# ESP32.net
KiCad netlist of a schematic drawn in EAGLE
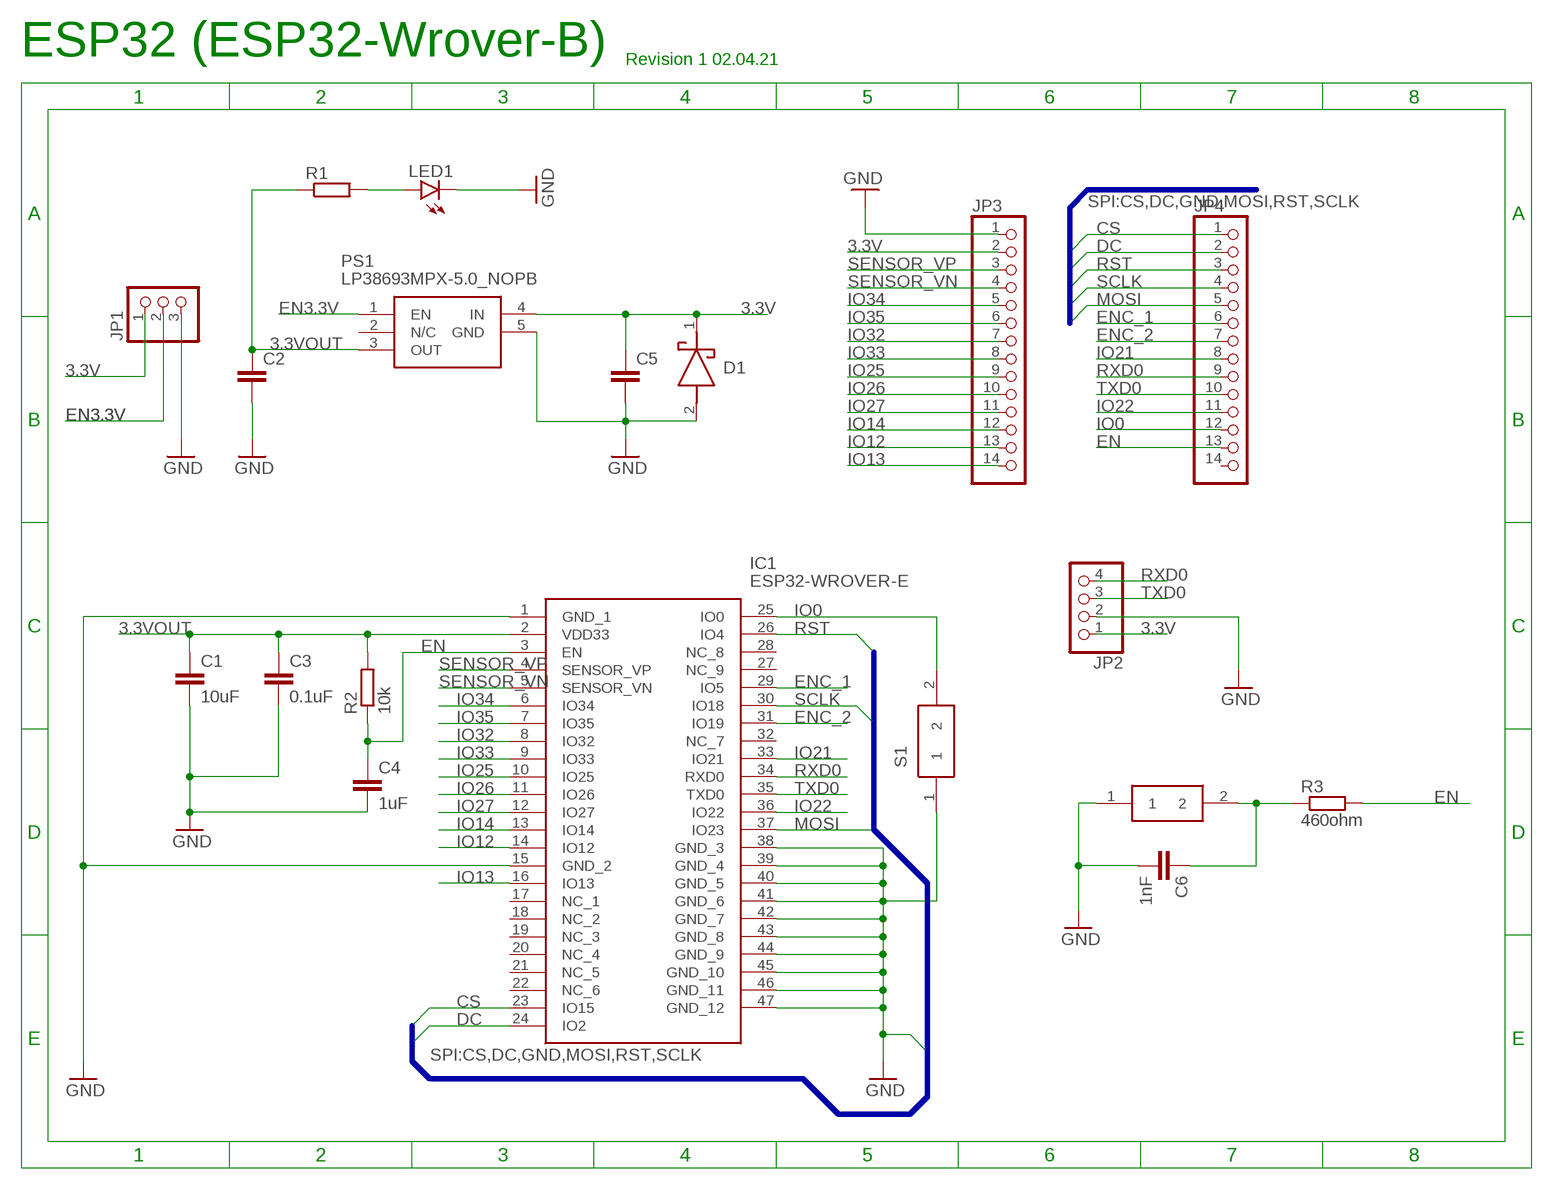
[diagram p0: schematic, sheet 1]

(export (version "E")
  (design (tool "Eeschema 10.0.6"))
  (components
    (comp (ref "C1")
      (value "10uF")
      (footprint "eagle-import:C1206")
      (libsource (lib "eagle-import") (part "C-EU_1206C1206"))
    )
    (comp (ref "C2")
      (value "C-EUC0805")
      (footprint "eagle-import:C0805")
      (libsource (lib "eagle-import") (part "C-EUC0805"))
    )
    (comp (ref "C3")
      (value "0.1uF")
      (footprint "eagle-import:C0805")
      (libsource (lib "eagle-import") (part "C-EU_805C0805"))
    )
    (comp (ref "C4")
      (value "1uF")
      (footprint "eagle-import:C0805")
      (libsource (lib "eagle-import") (part "C-EU_805C0805"))
    )
    (comp (ref "C5")
      (value "C-EUC0805")
      (footprint "eagle-import:C0805")
      (libsource (lib "eagle-import") (part "C-EUC0805"))
    )
    (comp (ref "C6")
      (value "1nF")
      (footprint "eagle-import:C0805")
      (libsource (lib "eagle-import") (part "C-EU_805C0805"))
    )
    (comp (ref "D1")
      (value "LSM115JE3_TR13")
      (footprint "eagle-import:DIOM5436X330N")
      (fields
        (field (name "MANUFACTURER_PART_NUMBER") "LSM115JE3/TR13")
        (field (name "MOUSER_PART_NUMBER") "494-LSM115JE3/TR13")
      )
      (libsource (lib "eagle-import") (part "LSM115JE3_TR13"))
    )
    (comp (ref "IC1")
      (value "ESP32-WROVER-E")
      (footprint "eagle-import:ESP32WROVERBM213DH6464PC3Q0")
      (fields (field (name "MANUFACTURER_PART_NUMBER") "ESP32-WROVER-E(M213EH3264PH3Q0) "))
      (libsource (lib "eagle-import") (part "ESP32-WROVER-E"))
    )
    (comp (ref "JP1")
      (value "PINHD-1X3")
      (footprint "eagle-import:1X03")
      (libsource (lib "eagle-import") (part "PINHD-1X3"))
    )
    (comp (ref "JP2")
      (value "PINHD-1X4")
      (footprint "eagle-import:1X04")
      (libsource (lib "eagle-import") (part "PINHD-1X4"))
    )
    (comp (ref "JP3")
      (value "PINHD-1X14")
      (footprint "eagle-import:1X14")
      (libsource (lib "eagle-import") (part "PINHD-1X14"))
    )
    (comp (ref "JP4")
      (value "PINHD-1X14")
      (footprint "eagle-import:1X14")
      (libsource (lib "eagle-import") (part "PINHD-1X14"))
    )
    (comp (ref "LED1")
      (value "LED_1206SMT1206")
      (footprint "eagle-import:1206")
      (libsource (lib "eagle-import") (part "LED_1206SMT1206"))
    )
    (comp (ref "PS1")
      (value "LP38693MPX-5.0_NOPB")
      (footprint "eagle-import:SOT150P700X160-5N")
      (libsource (lib "eagle-import") (part "LP38693MPX-5.0_NOPB"))
    )
    (comp (ref "R1")
      (value "R-EU_R0805")
      (footprint "eagle-import:R0805")
      (libsource (lib "eagle-import") (part "R-EU_R0805"))
    )
    (comp (ref "R2")
      (value "10k")
      (footprint "eagle-import:R0805")
      (libsource (lib "eagle-import") (part "R-EU_805R0805"))
    )
    (comp (ref "R3")
      (value "460ohm")
      (footprint "eagle-import:R0805")
      (libsource (lib "eagle-import") (part "R-EU_805R0805"))
    )
    (comp (ref "S1")
      (value "FSMSMTR")
      (footprint "eagle-import:FSMSM")
      (fields (field (name "MOUSER_PART_NUMBER") "506-FSMSMTR") (field (name "RS_PART_NUMBER") "1680547"))
      (libsource (lib "eagle-import") (part "FSMSMTR"))
    )
    (comp (ref "S2")
      (value "FSMSMTR")
      (footprint "eagle-import:FSMSM")
      (fields (field (name "MOUSER_PART_NUMBER") "506-FSMSMTR") (field (name "RS_PART_NUMBER") "1680547"))
      (libsource (lib "eagle-import") (part "FSMSMTR"))
    )
  )
  (nets
    (net (code "2") (name "/3.3V") (class "Default")
      (node (ref "C5") (pin "1") (pinfunction "1_1") (pintype "passive"))
      (node (ref "D1") (pin "1") (pinfunction "K_1") (pintype "bidirectional"))
      (node (ref "JP1") (pin "1") (pinfunction "1_1") (pintype "passive"))
      (node (ref "JP2") (pin "1") (pinfunction "1_1") (pintype "passive"))
      (node (ref "JP3") (pin "2") (pinfunction "2_2") (pintype "passive"))
      (node (ref "PS1") (pin "4") (pinfunction "IN_4") (pintype "bidirectional"))
    )
    (net (code "3") (name "/3.3VOUT") (class "Default")
      (node (ref "C1") (pin "1") (pinfunction "1_1") (pintype "passive"))
      (node (ref "C2") (pin "1") (pinfunction "1_1") (pintype "passive"))
      (node (ref "C3") (pin "1") (pinfunction "1_1") (pintype "passive"))
      (node (ref "IC1") (pin "2") (pinfunction "VDD33_2") (pintype "bidirectional"))
      (node (ref "PS1") (pin "3") (pinfunction "OUT_3") (pintype "bidirectional"))
      (node (ref "R1") (pin "1") (pinfunction "1_1") (pintype "passive"))
      (node (ref "R2") (pin "2") (pinfunction "2_2") (pintype "passive"))
    )
    (net (code "4") (name "/CS") (class "Default")
      (node (ref "IC1") (pin "23") (pinfunction "IO15_23") (pintype "bidirectional"))
      (node (ref "JP4") (pin "1") (pinfunction "1_1") (pintype "passive"))
    )
    (net (code "5") (name "/DC") (class "Default")
      (node (ref "IC1") (pin "24") (pinfunction "IO2_24") (pintype "bidirectional"))
      (node (ref "JP4") (pin "2") (pinfunction "2_2") (pintype "passive"))
    )
    (net (code "6") (name "/EN") (class "Default")
      (node (ref "C4") (pin "1") (pinfunction "1_1") (pintype "passive"))
      (node (ref "IC1") (pin "3") (pinfunction "EN_3") (pintype "bidirectional"))
      (node (ref "JP4") (pin "13") (pinfunction "13_13") (pintype "passive"))
      (node (ref "R2") (pin "1") (pinfunction "1_1") (pintype "passive"))
      (node (ref "R3") (pin "2") (pinfunction "2_2") (pintype "passive"))
    )
    (net (code "7") (name "/EN3.3V") (class "Default")
      (node (ref "JP1") (pin "2") (pinfunction "2_2") (pintype "passive"))
      (node (ref "PS1") (pin "1") (pinfunction "EN_1") (pintype "bidirectional"))
    )
    (net (code "8") (name "/ENC_1") (class "Default")
      (node (ref "IC1") (pin "29") (pinfunction "IO5_29") (pintype "bidirectional"))
      (node (ref "JP4") (pin "6") (pinfunction "6_6") (pintype "passive"))
    )
    (net (code "9") (name "/ENC_2") (class "Default")
      (node (ref "IC1") (pin "31") (pinfunction "IO19_31") (pintype "bidirectional"))
      (node (ref "JP4") (pin "7") (pinfunction "7_7") (pintype "passive"))
    )
    (net (code "10") (name "/IO0") (class "Default")
      (node (ref "IC1") (pin "25") (pinfunction "IO0_25") (pintype "bidirectional"))
      (node (ref "JP4") (pin "12") (pinfunction "12_12") (pintype "passive"))
      (node (ref "S1") (pin "2") (pinfunction "2_2") (pintype "bidirectional"))
    )
    (net (code "11") (name "/IO12") (class "Default")
      (node (ref "IC1") (pin "14") (pinfunction "IO12_14") (pintype "bidirectional"))
      (node (ref "JP3") (pin "13") (pinfunction "13_13") (pintype "passive"))
    )
    (net (code "12") (name "/IO13") (class "Default")
      (node (ref "IC1") (pin "16") (pinfunction "IO13_16") (pintype "bidirectional"))
      (node (ref "JP3") (pin "14") (pinfunction "14_14") (pintype "passive"))
    )
    (net (code "13") (name "/IO14") (class "Default")
      (node (ref "IC1") (pin "13") (pinfunction "IO14_13") (pintype "bidirectional"))
      (node (ref "JP3") (pin "12") (pinfunction "12_12") (pintype "passive"))
    )
    (net (code "14") (name "/IO21") (class "Default")
      (node (ref "IC1") (pin "33") (pinfunction "IO21_33") (pintype "bidirectional"))
      (node (ref "JP4") (pin "8") (pinfunction "8_8") (pintype "passive"))
    )
    (net (code "15") (name "/IO22") (class "Default")
      (node (ref "IC1") (pin "36") (pinfunction "IO22_36") (pintype "bidirectional"))
      (node (ref "JP4") (pin "11") (pinfunction "11_11") (pintype "passive"))
    )
    (net (code "16") (name "/IO25") (class "Default")
      (node (ref "IC1") (pin "10") (pinfunction "IO25_10") (pintype "bidirectional"))
      (node (ref "JP3") (pin "9") (pinfunction "9_9") (pintype "passive"))
    )
    (net (code "17") (name "/IO26") (class "Default")
      (node (ref "IC1") (pin "11") (pinfunction "IO26_11") (pintype "bidirectional"))
      (node (ref "JP3") (pin "10") (pinfunction "10_10") (pintype "passive"))
    )
    (net (code "18") (name "/IO27") (class "Default")
      (node (ref "IC1") (pin "12") (pinfunction "IO27_12") (pintype "bidirectional"))
      (node (ref "JP3") (pin "11") (pinfunction "11_11") (pintype "passive"))
    )
    (net (code "19") (name "/IO32") (class "Default")
      (node (ref "IC1") (pin "8") (pinfunction "IO32_8") (pintype "bidirectional"))
      (node (ref "JP3") (pin "7") (pinfunction "7_7") (pintype "passive"))
    )
    (net (code "20") (name "/IO33") (class "Default")
      (node (ref "IC1") (pin "9") (pinfunction "IO33_9") (pintype "bidirectional"))
      (node (ref "JP3") (pin "8") (pinfunction "8_8") (pintype "passive"))
    )
    (net (code "21") (name "/IO34") (class "Default")
      (node (ref "IC1") (pin "6") (pinfunction "IO34_6") (pintype "bidirectional"))
      (node (ref "JP3") (pin "5") (pinfunction "5_5") (pintype "passive"))
    )
    (net (code "22") (name "/IO35") (class "Default")
      (node (ref "IC1") (pin "7") (pinfunction "IO35_7") (pintype "bidirectional"))
      (node (ref "JP3") (pin "6") (pinfunction "6_6") (pintype "passive"))
    )
    (net (code "23") (name "/MOSI") (class "Default")
      (node (ref "IC1") (pin "37") (pinfunction "IO23_37") (pintype "bidirectional"))
      (node (ref "JP4") (pin "5") (pinfunction "5_5") (pintype "passive"))
    )
    (net (code "24") (name "/RST") (class "Default")
      (node (ref "IC1") (pin "26") (pinfunction "IO4_26") (pintype "bidirectional"))
      (node (ref "JP4") (pin "3") (pinfunction "3_3") (pintype "passive"))
    )
    (net (code "25") (name "/RXD0") (class "Default")
      (node (ref "IC1") (pin "34") (pinfunction "RXD0_34") (pintype "bidirectional"))
      (node (ref "JP2") (pin "4") (pinfunction "4_4") (pintype "passive"))
      (node (ref "JP4") (pin "9") (pinfunction "9_9") (pintype "passive"))
    )
    (net (code "26") (name "/SCLK") (class "Default")
      (node (ref "IC1") (pin "30") (pinfunction "IO18_30") (pintype "bidirectional"))
      (node (ref "JP4") (pin "4") (pinfunction "4_4") (pintype "passive"))
    )
    (net (code "27") (name "/SENSOR_VN") (class "Default")
      (node (ref "IC1") (pin "5") (pinfunction "SENSOR_VN_5") (pintype "bidirectional"))
      (node (ref "JP3") (pin "4") (pinfunction "4_4") (pintype "passive"))
    )
    (net (code "28") (name "/SENSOR_VP") (class "Default")
      (node (ref "IC1") (pin "4") (pinfunction "SENSOR_VP_4") (pintype "bidirectional"))
      (node (ref "JP3") (pin "3") (pinfunction "3_3") (pintype "passive"))
    )
    (net (code "29") (name "/TXD0") (class "Default")
      (node (ref "IC1") (pin "35") (pinfunction "TXD0_35") (pintype "bidirectional"))
      (node (ref "JP2") (pin "3") (pinfunction "3_3") (pintype "passive"))
      (node (ref "JP4") (pin "10") (pinfunction "10_10") (pintype "passive"))
    )
    (net (code "31") (name "GND") (class "Default")
      (node (ref "C1") (pin "2") (pinfunction "2_2") (pintype "passive"))
      (node (ref "C2") (pin "2") (pinfunction "2_2") (pintype "passive"))
      (node (ref "C3") (pin "2") (pinfunction "2_2") (pintype "passive"))
      (node (ref "C4") (pin "2") (pinfunction "2_2") (pintype "passive"))
      (node (ref "C5") (pin "2") (pinfunction "2_2") (pintype "passive"))
      (node (ref "C6") (pin "2") (pinfunction "2_2") (pintype "passive"))
      (node (ref "D1") (pin "2") (pinfunction "A_2") (pintype "bidirectional"))
      (node (ref "IC1") (pin "1") (pinfunction "GND_1_1") (pintype "bidirectional"))
      (node (ref "IC1") (pin "15") (pinfunction "GND_2_15") (pintype "bidirectional"))
      (node (ref "IC1") (pin "38") (pinfunction "GND_3_38") (pintype "bidirectional"))
      (node (ref "IC1") (pin "39") (pinfunction "GND_4_39") (pintype "bidirectional"))
      (node (ref "IC1") (pin "40") (pinfunction "GND_5_40") (pintype "bidirectional"))
      (node (ref "IC1") (pin "41") (pinfunction "GND_6_41") (pintype "bidirectional"))
      (node (ref "IC1") (pin "42") (pinfunction "GND_7_42") (pintype "bidirectional"))
      (node (ref "IC1") (pin "43") (pinfunction "GND_8_43") (pintype "bidirectional"))
      (node (ref "IC1") (pin "44") (pinfunction "GND_9_44") (pintype "bidirectional"))
      (node (ref "IC1") (pin "45") (pinfunction "GND_10_45") (pintype "bidirectional"))
      (node (ref "IC1") (pin "46") (pinfunction "GND_11_46") (pintype "bidirectional"))
      (node (ref "IC1") (pin "47") (pinfunction "GND_12_47") (pintype "bidirectional"))
      (node (ref "JP1") (pin "3") (pinfunction "3_3") (pintype "passive"))
      (node (ref "JP2") (pin "2") (pinfunction "2_2") (pintype "passive"))
      (node (ref "JP3") (pin "1") (pinfunction "1_1") (pintype "passive"))
      (node (ref "LED1") (pin "C") (pinfunction "C_C") (pintype "passive"))
      (node (ref "PS1") (pin "5") (pinfunction "GND_5") (pintype "bidirectional"))
      (node (ref "S1") (pin "1") (pinfunction "1_1") (pintype "bidirectional"))
      (node (ref "S2") (pin "1") (pinfunction "1_1") (pintype "bidirectional"))
    )
    (net (code "32") (name "Net-(C6-Pad1)") (class "Default")
      (node (ref "C6") (pin "1") (pinfunction "1_1") (pintype "passive"))
      (node (ref "R3") (pin "1") (pinfunction "1_1") (pintype "passive"))
      (node (ref "S2") (pin "2") (pinfunction "2_2") (pintype "bidirectional"))
    )
    (net (code "33") (name "Net-(LED1-PadA)") (class "Default")
      (node (ref "LED1") (pin "A") (pinfunction "A_A") (pintype "passive"))
      (node (ref "R1") (pin "2") (pinfunction "2_2") (pintype "passive"))
    )
    (net (code "34") (name "unconnected-(IC1-NC_1-Pad17)") (class "Default")
      (node (ref "IC1") (pin "17") (pinfunction "NC_1_17") (pintype "no_connect"))
    )
    (net (code "35") (name "unconnected-(IC1-NC_2-Pad18)") (class "Default")
      (node (ref "IC1") (pin "18") (pinfunction "NC_2_18") (pintype "no_connect"))
    )
    (net (code "36") (name "unconnected-(IC1-NC_3-Pad19)") (class "Default")
      (node (ref "IC1") (pin "19") (pinfunction "NC_3_19") (pintype "no_connect"))
    )
    (net (code "37") (name "unconnected-(IC1-NC_4-Pad20)") (class "Default")
      (node (ref "IC1") (pin "20") (pinfunction "NC_4_20") (pintype "no_connect"))
    )
    (net (code "38") (name "unconnected-(IC1-NC_5-Pad21)") (class "Default")
      (node (ref "IC1") (pin "21") (pinfunction "NC_5_21") (pintype "no_connect"))
    )
    (net (code "39") (name "unconnected-(IC1-NC_6-Pad22)") (class "Default")
      (node (ref "IC1") (pin "22") (pinfunction "NC_6_22") (pintype "no_connect"))
    )
    (net (code "40") (name "unconnected-(IC1-NC_7-Pad32)") (class "Default")
      (node (ref "IC1") (pin "32") (pinfunction "NC_7_32") (pintype "no_connect"))
    )
    (net (code "41") (name "unconnected-(IC1-NC_8-Pad28)") (class "Default")
      (node (ref "IC1") (pin "28") (pinfunction "NC_8_28") (pintype "no_connect"))
    )
    (net (code "42") (name "unconnected-(IC1-NC_9-Pad27)") (class "Default")
      (node (ref "IC1") (pin "27") (pinfunction "NC_9_27") (pintype "no_connect"))
    )
    (net (code "43") (name "unconnected-(JP4-Pad14)") (class "Default")
      (node (ref "JP4") (pin "14") (pinfunction "14_14") (pintype "passive"))
    )
    (net (code "44") (name "unconnected-(PS1-N{slash}C-Pad2)") (class "Default")
      (node (ref "PS1") (pin "2") (pinfunction "N/C_2") (pintype "no_connect"))
    )
  )
)
